# TP4056.net
KiCad netlist of a schematic drawn in Altium Designer
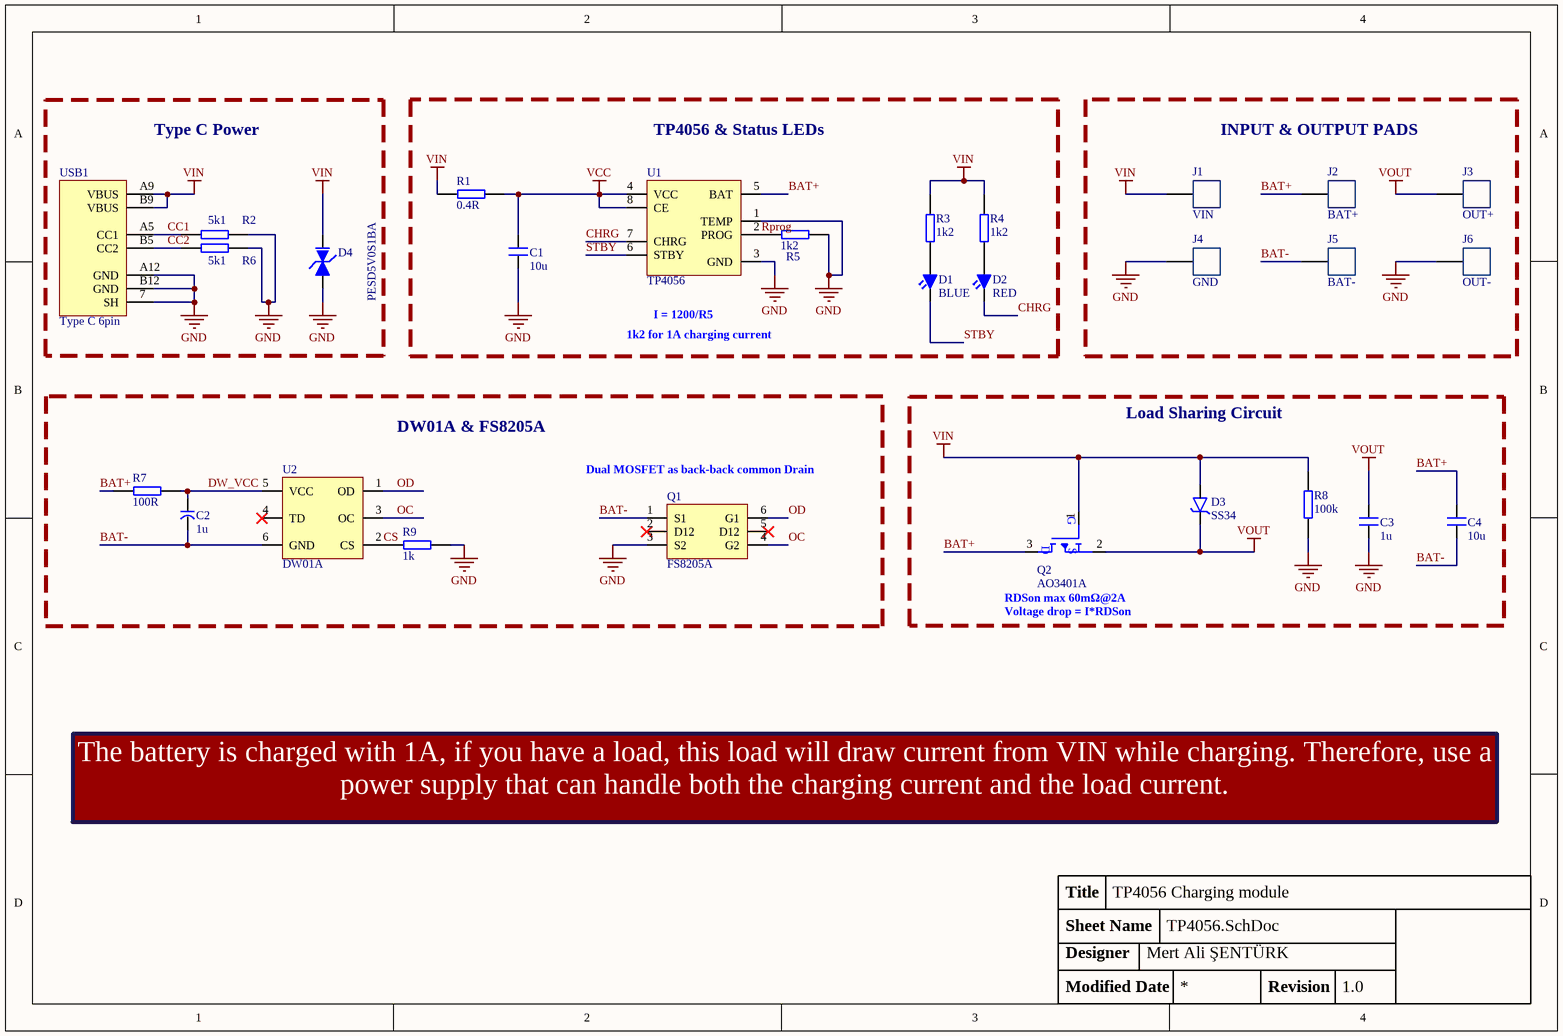
[diagram p0: TP4056.SchDoc]

(export (version "E")
  (design (tool "Eeschema 10.0.6"))
  (components
    (comp (ref "C1")
      (value "10u")
      (footprint "0603 CAP")
      (description "CL10A106MA8NRNC")
      (libsource (lib "GenerALI") (part "0603 100p CAP"))
    )
    (comp (ref "C2")
      (value "1u")
      (footprint "3216 cap")
      (libsource (lib "GenerALI") (part "3216 Tantal Cap SMD"))
    )
    (comp (ref "C3") (value "1u") (footprint "0805 CAP") (libsource (lib "GenerALI") (part "0805 10u CAP")))
    (comp (ref "C4")
      (value "10u")
      (footprint "0603 CAP")
      (description "CL10A106MA8NRNC")
      (libsource (lib "GenerALI") (part "0603 100p CAP"))
    )
    (comp (ref "D1")
      (value "BLUE")
      (footprint "LED 0805")
      (libsource (lib "GenerALI") (part "LED GREEN 0805"))
    )
    (comp (ref "D2") (value "RED") (footprint "LED 0805") (libsource (lib "GenerALI") (part "LED RED 0805")))
    (comp (ref "D3")
      (value "SS34")
      (footprint "SMA/DO-214AC")
      (description "40V Independent Type 3A 550mV@3A SMA(DO-214AC) Schottky Diodes ROHS")
      (libsource (lib "GenerALI") (part "SS34"))
    )
    (comp (ref "D4")
      (value "PESD5V0S1BA")
      (footprint "SOD-323")
      (description "11A 8V 5.6V Bidirectional 5V SOD-323  ESD and Surge Protection (TVS/ESD) ROHS")
      (libsource (lib "GenerALI") (part "PESD5V0S1BA"))
    )
    (comp (ref "J1")
      (value "VIN")
      (footprint "PAD")
      (description "Solder pad")
      (libsource (lib "GenerALI") (part "PAD"))
    )
    (comp (ref "J2")
      (value "BAT+")
      (footprint "PAD")
      (description "Solder pad")
      (libsource (lib "GenerALI") (part "PAD"))
    )
    (comp (ref "J3")
      (value "OUT+")
      (footprint "PAD")
      (description "Solder pad")
      (libsource (lib "GenerALI") (part "PAD"))
    )
    (comp (ref "J4")
      (value "GND")
      (footprint "PAD")
      (description "Solder pad")
      (libsource (lib "GenerALI") (part "PAD"))
    )
    (comp (ref "J5")
      (value "BAT-")
      (footprint "PAD")
      (description "Solder pad")
      (libsource (lib "GenerALI") (part "PAD"))
    )
    (comp (ref "J6")
      (value "OUT-")
      (footprint "PAD")
      (description "Solder pad")
      (libsource (lib "GenerALI") (part "PAD"))
    )
    (comp (ref "Q1")
      (value "FS8205A")
      (footprint "SOT23-6")
      (description "20V 6A 18mΩ@4.5V,6A 1.5W 1.2V@250uA 2 N-Channel SOT-23-6L MOSFETs ROHS")
      (libsource (lib "GenerALI") (part "FS8205A"))
    )
    (comp (ref "Q2")
      (value "AO3401A")
      (footprint "SOT23")
      (description "30V 4A 44mΩ@10V,4.3A 1.4W 1.3V@250uA 1 Piece P-Channel SOT-23 MOSFETs ROHS")
      (libsource (lib "GenerALI") (part "AO3401A"))
    )
    (comp (ref "R1")
      (value "0.4R")
      (footprint "2512 RES")
      (description "25121WJ040KT4E")
      (libsource (lib "GenerALI") (part "2512 RES"))
    )
    (comp (ref "R2") (value "5k1") (footprint "0603 RES") (libsource (lib "GenerALI") (part "0603 0R RES")))
    (comp (ref "R3")
      (value "1k2")
      (footprint "0603 RES")
      (description "0603WAF1201T5E")
      (libsource (lib "GenerALI") (part "0603 1k RES"))
    )
    (comp (ref "R4")
      (value "1k2")
      (footprint "0603 RES")
      (description "0603WAF1201T5E")
      (libsource (lib "GenerALI") (part "0603 1k RES"))
    )
    (comp (ref "R5")
      (value "1k2")
      (footprint "0603 RES")
      (description "0603WAF1201T5E")
      (libsource (lib "GenerALI") (part "0603 1k RES"))
    )
    (comp (ref "R6") (value "5k1") (footprint "0603 RES") (libsource (lib "GenerALI") (part "0603 0R RES")))
    (comp (ref "R7") (value "100R") (footprint "0603 RES") (libsource (lib "GenerALI") (part "0603 1k RES")))
    (comp (ref "R8")
      (value "100k")
      (footprint "0603 RES")
      (libsource (lib "GenerALI") (part "0603 100R RES"))
    )
    (comp (ref "R9") (value "1k") (footprint "0603 RES") (libsource (lib "GenerALI") (part "0603 1k RES")))
    (comp (ref "U1")
      (value "TP4056")
      (footprint "SOP-8")
      (description "1A Standalone Linear Li-lon Battery Charger with Thermal Regulation")
      (libsource (lib "GenerALI") (part "TP4056"))
    )
    (comp (ref "U2")
      (value "DW01A")
      (footprint "SOT23-6")
      (description "BATTERY PROTECTION IC IN A SOT23")
      (libsource (lib "GenerALI") (part "DW01A"))
    )
    (comp (ref "USB1")
      (value "Type C 6pin")
      (footprint "TYPE-C 6P(073)")
      (description "Manufacturer SHOU HAN\r\nMFR.Part # TYPE-C 6P(073)\r\nJLCPCB Part # C668623")
      (fields (field (name "MANUFACTURER") "SHOU HAN") (field (name "JLCPCB PART") "C668623"))
      (libsource (lib "GenerALI") (part "USB TYPE-C 6P(073) (Right Angle)"))
    )
  )
  (nets
    (net (code "1") (name "/BAT+") (class "Default")
      (node (ref "C4") (pin "2") (pinfunction "2_2") (pintype "passive"))
      (node (ref "J2") (pin "1") (pinfunction "1_1") (pintype "passive"))
      (node (ref "Q2") (pin "3") (pinfunction "3_3") (pintype "passive"))
      (node (ref "R7") (pin "1") (pinfunction "1_1") (pintype "passive"))
      (node (ref "U1") (pin "5") (pinfunction "BAT_5") (pintype "passive"))
    )
    (net (code "2") (name "/BAT-") (class "Default")
      (node (ref "C2") (pin "2") (pinfunction "2_2") (pintype "passive"))
      (node (ref "C4") (pin "1") (pinfunction "1_1") (pintype "passive"))
      (node (ref "J5") (pin "1") (pinfunction "1_1") (pintype "passive"))
      (node (ref "Q1") (pin "1") (pinfunction "S1_1") (pintype "passive"))
      (node (ref "U2") (pin "6") (pinfunction "GND_6") (pintype "passive"))
    )
    (net (code "3") (name "/CC1") (class "Default")
      (node (ref "R2") (pin "1") (pinfunction "1_1") (pintype "passive"))
      (node (ref "USB1") (pin "A5") (pinfunction "CC1_A5") (pintype "passive"))
    )
    (net (code "4") (name "/CC2") (class "Default")
      (node (ref "R6") (pin "1") (pinfunction "1_1") (pintype "passive"))
      (node (ref "USB1") (pin "B5") (pinfunction "CC2_B5") (pintype "passive"))
    )
    (net (code "5") (name "/CHRG") (class "Default")
      (node (ref "D2") (pin "1") (pinfunction "1_1") (pintype "passive"))
      (node (ref "U1") (pin "7") (pinfunction "CHRG_7") (pintype "passive"))
    )
    (net (code "6") (name "/CS") (class "Default")
      (node (ref "R9") (pin "1") (pinfunction "1_1") (pintype "passive"))
      (node (ref "U2") (pin "2") (pinfunction "CS_2") (pintype "passive"))
    )
    (net (code "7") (name "/DW_VCC") (class "Default")
      (node (ref "C2") (pin "1") (pinfunction "1_1") (pintype "passive"))
      (node (ref "R7") (pin "2") (pinfunction "2_2") (pintype "passive"))
      (node (ref "U2") (pin "5") (pinfunction "VCC_5") (pintype "passive"))
    )
    (net (code "8") (name "/OC") (class "Default")
      (node (ref "Q1") (pin "4") (pinfunction "G2_4") (pintype "passive"))
      (node (ref "U2") (pin "3") (pinfunction "OC_3") (pintype "passive"))
    )
    (net (code "9") (name "/OD") (class "Default")
      (node (ref "Q1") (pin "6") (pinfunction "G1_6") (pintype "passive"))
      (node (ref "U2") (pin "1") (pinfunction "OD_1") (pintype "passive"))
    )
    (net (code "10") (name "/Rprog") (class "Default")
      (node (ref "R5") (pin "1") (pinfunction "1_1") (pintype "passive"))
      (node (ref "U1") (pin "2") (pinfunction "PROG_2") (pintype "passive"))
    )
    (net (code "11") (name "/STBY") (class "Default")
      (node (ref "D1") (pin "1") (pinfunction "1_1") (pintype "passive"))
      (node (ref "U1") (pin "6") (pinfunction "STBY_6") (pintype "passive"))
    )
    (net (code "12") (name "GND") (class "Default")
      (node (ref "C1") (pin "1") (pinfunction "1_1") (pintype "passive"))
      (node (ref "C3") (pin "1") (pinfunction "1_1") (pintype "passive"))
      (node (ref "D4") (pin "2") (pinfunction "2_2") (pintype "passive"))
      (node (ref "J4") (pin "1") (pinfunction "1_1") (pintype "passive"))
      (node (ref "J6") (pin "1") (pinfunction "1_1") (pintype "passive"))
      (node (ref "Q1") (pin "3") (pinfunction "S2_3") (pintype "passive"))
      (node (ref "R2") (pin "2") (pinfunction "2_2") (pintype "passive"))
      (node (ref "R5") (pin "2") (pinfunction "2_2") (pintype "passive"))
      (node (ref "R6") (pin "2") (pinfunction "2_2") (pintype "passive"))
      (node (ref "R8") (pin "1") (pinfunction "1_1") (pintype "passive"))
      (node (ref "R9") (pin "2") (pinfunction "2_2") (pintype "passive"))
      (node (ref "U1") (pin "1") (pinfunction "TEMP_1") (pintype "passive"))
      (node (ref "U1") (pin "3") (pinfunction "GND_3") (pintype "passive"))
      (node (ref "USB1") (pin "7") (pinfunction "SH_7") (pintype "passive"))
      (node (ref "USB1") (pin "A12") (pinfunction "GND_A12") (pintype "passive"))
      (node (ref "USB1") (pin "B12") (pinfunction "GND_B12") (pintype "passive"))
    )
    (net (code "13") (name "Net-(D1-Pad2)") (class "Default")
      (node (ref "D1") (pin "2") (pinfunction "2_2") (pintype "passive"))
      (node (ref "R3") (pin "1") (pinfunction "1_1") (pintype "passive"))
    )
    (net (code "14") (name "Net-(D2-Pad2)") (class "Default")
      (node (ref "D2") (pin "2") (pinfunction "2_2") (pintype "passive"))
      (node (ref "R4") (pin "1") (pinfunction "1_1") (pintype "passive"))
    )
    (net (code "15") (name "VCC") (class "Default")
      (node (ref "C1") (pin "2") (pinfunction "2_2") (pintype "passive"))
      (node (ref "R1") (pin "1") (pinfunction "1_1") (pintype "passive"))
      (node (ref "U1") (pin "4") (pinfunction "VCC_4") (pintype "passive"))
      (node (ref "U1") (pin "8") (pinfunction "CE_8") (pintype "passive"))
    )
    (net (code "16") (name "VIN") (class "Default")
      (node (ref "D3") (pin "2") (pinfunction "2_2") (pintype "passive"))
      (node (ref "D4") (pin "1") (pinfunction "1_1") (pintype "passive"))
      (node (ref "J1") (pin "1") (pinfunction "1_1") (pintype "passive"))
      (node (ref "Q2") (pin "1") (pinfunction "1_1") (pintype "passive"))
      (node (ref "R1") (pin "2") (pinfunction "2_2") (pintype "passive"))
      (node (ref "R3") (pin "2") (pinfunction "2_2") (pintype "passive"))
      (node (ref "R4") (pin "2") (pinfunction "2_2") (pintype "passive"))
      (node (ref "R8") (pin "2") (pinfunction "2_2") (pintype "passive"))
      (node (ref "USB1") (pin "A9") (pinfunction "VBUS_A9") (pintype "passive"))
      (node (ref "USB1") (pin "B9") (pinfunction "VBUS_B9") (pintype "passive"))
    )
    (net (code "17") (name "VOUT") (class "Default")
      (node (ref "C3") (pin "2") (pinfunction "2_2") (pintype "passive"))
      (node (ref "D3") (pin "1") (pinfunction "1_1") (pintype "passive"))
      (node (ref "J3") (pin "1") (pinfunction "1_1") (pintype "passive"))
      (node (ref "Q2") (pin "2") (pinfunction "2_2") (pintype "passive"))
    )
    (net (code "18") (name "unconnected-(Q1-D12-Pad2)") (class "Default")
      (node (ref "Q1") (pin "2") (pinfunction "D12_2") (pintype "passive+no_connect"))
    )
    (net (code "19") (name "unconnected-(Q1-D12-Pad5)") (class "Default")
      (node (ref "Q1") (pin "5") (pinfunction "D12_5") (pintype "passive+no_connect"))
    )
    (net (code "20") (name "unconnected-(U2-TD-Pad4)") (class "Default")
      (node (ref "U2") (pin "4") (pinfunction "TD_4") (pintype "passive+no_connect"))
    )
  )
)
